# PWM_Channel.net
KiCad netlist of a schematic drawn in Altium Designer
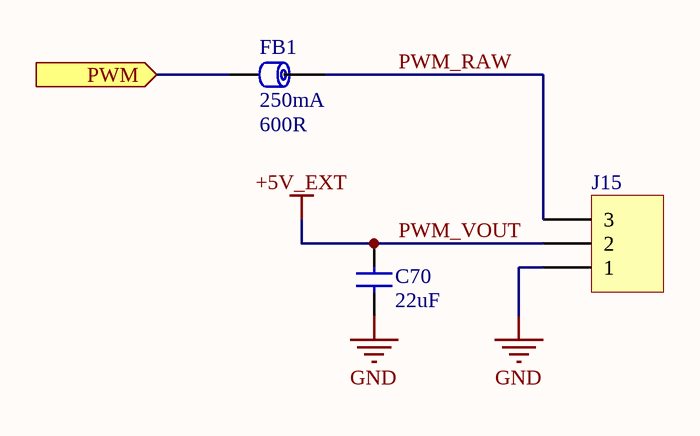
[diagram p0: PWM_Channel.SchDoc]

(export (version "E")
  (design (tool "Eeschema 10.0.6"))
  (components
    (comp (ref "C70")
      (value "22uF")
      (footprint "0805_Capacitor")
      (description "CAP CERM 22uF 20% 16V 0805")
      (fields (field (name "VOLTAGE") "16V") (field (name "Comment") "CAP 22uF 16V X5R"))
      (libsource (lib "capacitor") (part "C_0805_22uF_16V_20%"))
    )
    (comp (ref "FB1")
      (value "600R")
      (footprint "0402_Inductor")
      (description "600 Ohms @ 100MHz 1 Ferrite Bead 0402 (1005 Metric) 250mA 500mOhm")
      (fields
        (field (name "MANUFACTURER") "Taiyo Yuden")
        (field (name "MANUFACTURER PART NUMBER") "BK1005HM601-T")
        (field (name "CURRENT RATING") "250mA")
      )
      (libsource (lib "inductor") (part "FB_0402_600R_250mA"))
    )
    (comp (ref "J15")
      (value "Header 3")
      (footprint "HDR1X3")
      (description "Header, 3-Pin")
      (fields (field (name "PUBLISHER") "Altium Limited"))
      (libsource (lib "Miscellaneous Connectors") (part "Header 3"))
    )
  )
  (nets
    (net (code "1") (name "+5V_EXT") (class "Default")
      (node (ref "C70") (pin "1") (pinfunction "1_1") (pintype "passive"))
      (node (ref "J15") (pin "2") (pinfunction "2_2") (pintype "passive"))
    )
    (net (code "2") (name "/PWM") (class "Default")
      (node (ref "FB1") (pin "1") (pinfunction "1_1") (pintype "passive"))
    )
    (net (code "3") (name "/PWM_RAW") (class "Default")
      (node (ref "FB1") (pin "2") (pinfunction "2_2") (pintype "passive"))
      (node (ref "J15") (pin "3") (pinfunction "3_3") (pintype "passive"))
    )
    (net (code "4") (name "GND") (class "Default")
      (node (ref "C70") (pin "2") (pinfunction "2_2") (pintype "passive"))
      (node (ref "J15") (pin "1") (pinfunction "1_1") (pintype "passive"))
    )
  )
)
